# Fanout_Buffer.net
KiCad netlist of a schematic drawn in Altium Designer
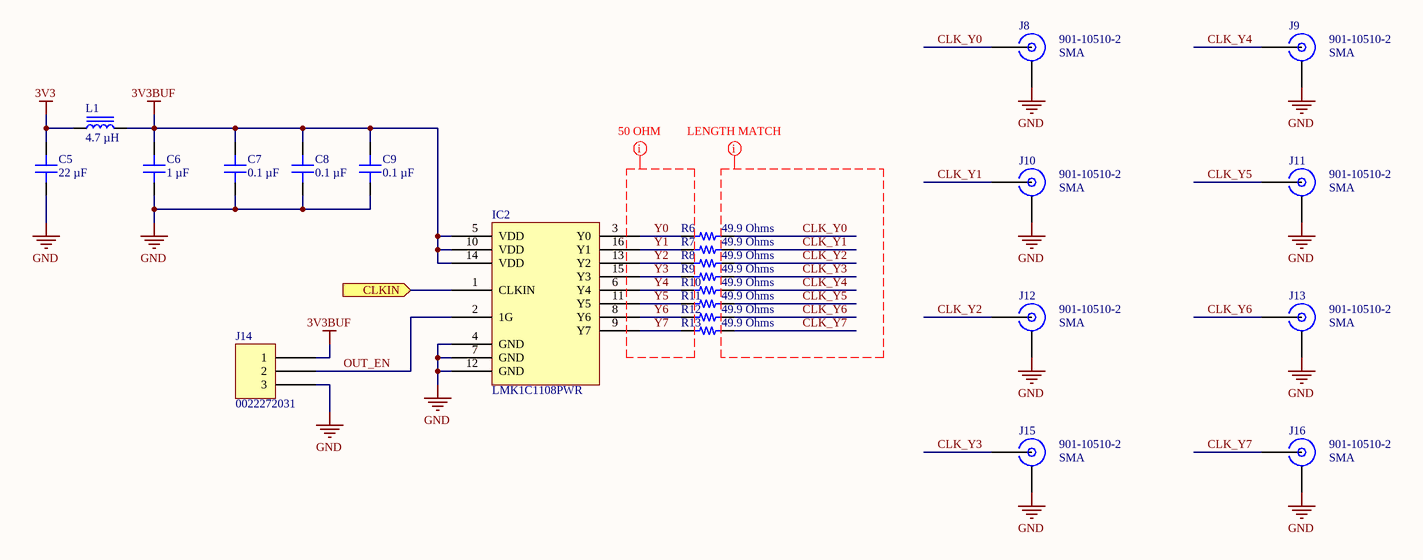
[diagram p0: Fanout Buffer.SchDoc]

(export (version "E")
  (design (tool "Eeschema 10.0.6"))
  (components
    (comp (ref "C5")
      (value "22 µF")
      (footprint "CAP 0603_1608")
      (description "CAP CER 22UF 10V X5R 0603")
      (fields
        (field (name "PART NUMBER") "CL10A226MP8NUNE")
        (field (name "MANUFACTURER") "Samsung Electro-Mechanics")
      )
      (libsource (lib "altiumlibrary.com") (part "Capacitor"))
    )
    (comp (ref "C6")
      (value "1 µF")
      (footprint "CAP 0603_1608")
      (description "CAP CER 1UF 25V X7R 0603")
      (fields
        (field (name "PART NUMBER") "GCM188R71E105KA64D")
        (field (name "MANUFACTURER") "Murata Electronics")
      )
      (libsource (lib "altiumlibrary.com") (part "Capacitor"))
    )
    (comp (ref "C7")
      (value "0.1 µF")
      (footprint "CAP 0603_1608")
      (description "CAP CER 0.1UF 50V X7R 0603")
      (fields
        (field (name "PART NUMBER") "CL10B104KB8NNNC")
        (field (name "MANUFACTURER") "Samsung Electro-Mechanics")
      )
      (libsource (lib "altiumlibrary.com") (part "Capacitor"))
    )
    (comp (ref "C8")
      (value "0.1 µF")
      (footprint "CAP 0603_1608")
      (description "CAP CER 0.1UF 50V X7R 0603")
      (fields
        (field (name "PART NUMBER") "CL10B104KB8NNNC")
        (field (name "MANUFACTURER") "Samsung Electro-Mechanics")
      )
      (libsource (lib "altiumlibrary.com") (part "Capacitor"))
    )
    (comp (ref "C9")
      (value "0.1 µF")
      (footprint "CAP 0603_1608")
      (description "CAP CER 0.1UF 50V X7R 0603")
      (fields
        (field (name "PART NUMBER") "CL10B104KB8NNNC")
        (field (name "MANUFACTURER") "Samsung Electro-Mechanics")
      )
      (libsource (lib "altiumlibrary.com") (part "Capacitor"))
    )
    (comp (ref "IC2")
      (value "LMK1C1108PWR")
      (footprint "TI TSSOP-16 PW0016A")
      (description "IC CLK BUFFER 1:8 250MHZ 16TSSOP")
      (fields (field (name "MANUFACTURER") "Texas Instruments"))
      (libsource (lib "altiumlibrary.com") (part "TI LMK1C1108 PW"))
    )
    (comp (ref "J8")
      (value "901-10510-2")
      (footprint "AMPHENOL 901-10510-2")
      (description "CONN SMA JACK R/A 50OHM EDGE MNT")
      (fields (field (name "CONNECTOR STYLE") "SMA") (field (name "MANUFACTURER") "Amphenol RF"))
      (libsource (lib "altiumlibrary.com") (part "COAXIAL JACK"))
    )
    (comp (ref "J9")
      (value "901-10510-2")
      (footprint "AMPHENOL 901-10510-2")
      (description "CONN SMA JACK R/A 50OHM EDGE MNT")
      (fields (field (name "CONNECTOR STYLE") "SMA") (field (name "MANUFACTURER") "Amphenol RF"))
      (libsource (lib "altiumlibrary.com") (part "COAXIAL JACK"))
    )
    (comp (ref "J10")
      (value "901-10510-2")
      (footprint "AMPHENOL 901-10510-2")
      (description "CONN SMA JACK R/A 50OHM EDGE MNT")
      (fields (field (name "CONNECTOR STYLE") "SMA") (field (name "MANUFACTURER") "Amphenol RF"))
      (libsource (lib "altiumlibrary.com") (part "COAXIAL JACK"))
    )
    (comp (ref "J11")
      (value "901-10510-2")
      (footprint "AMPHENOL 901-10510-2")
      (description "CONN SMA JACK R/A 50OHM EDGE MNT")
      (fields (field (name "CONNECTOR STYLE") "SMA") (field (name "MANUFACTURER") "Amphenol RF"))
      (libsource (lib "altiumlibrary.com") (part "COAXIAL JACK"))
    )
    (comp (ref "J12")
      (value "901-10510-2")
      (footprint "AMPHENOL 901-10510-2")
      (description "CONN SMA JACK R/A 50OHM EDGE MNT")
      (fields (field (name "CONNECTOR STYLE") "SMA") (field (name "MANUFACTURER") "Amphenol RF"))
      (libsource (lib "altiumlibrary.com") (part "COAXIAL JACK"))
    )
    (comp (ref "J13")
      (value "901-10510-2")
      (footprint "AMPHENOL 901-10510-2")
      (description "CONN SMA JACK R/A 50OHM EDGE MNT")
      (fields (field (name "CONNECTOR STYLE") "SMA") (field (name "MANUFACTURER") "Amphenol RF"))
      (libsource (lib "altiumlibrary.com") (part "COAXIAL JACK"))
    )
    (comp (ref "J14")
      (value "0022272031")
      (footprint "MOLEX KK 0022272031")
      (description "CONN HEADER VERT 3POS 2.54MM")
      (fields (field (name "MANUFACTURER") "Molex"))
      (libsource (lib "altiumlibrary.com") (part "3 Pin"))
    )
    (comp (ref "J15")
      (value "901-10510-2")
      (footprint "AMPHENOL 901-10510-2")
      (description "CONN SMA JACK R/A 50OHM EDGE MNT")
      (fields (field (name "CONNECTOR STYLE") "SMA") (field (name "MANUFACTURER") "Amphenol RF"))
      (libsource (lib "altiumlibrary.com") (part "COAXIAL JACK"))
    )
    (comp (ref "J16")
      (value "901-10510-2")
      (footprint "AMPHENOL 901-10510-2")
      (description "CONN SMA JACK R/A 50OHM EDGE MNT")
      (fields (field (name "CONNECTOR STYLE") "SMA") (field (name "MANUFACTURER") "Amphenol RF"))
      (libsource (lib "altiumlibrary.com") (part "COAXIAL JACK"))
    )
    (comp (ref "L1")
      (value "4.7 µH")
      (footprint "WURTH WE-LQS 3015")
      (description "FIXED IND 4.7UH 1.3A 96 MOHM SMD")
      (fields (field (name "PART NUMBER") "74404032047") (field (name "MANUFACTURER") "Würth Elektronik"))
      (libsource (lib "altiumlibrary.com") (part "Inductor"))
    )
    (comp (ref "R6")
      (value "49.9 Ohms")
      (footprint "RES 0402_1005")
      (description "RES SMD 49.9 OHM 1% 1/10W 0402")
      (fields
        (field (name "PART NUMBER") "ERJ-2RKF49R9X")
        (field (name "MANUFACTURER") "Panasonic Electronic Components")
      )
      (libsource (lib "altiumlibrary.com") (part "Resistor"))
    )
    (comp (ref "R7")
      (value "49.9 Ohms")
      (footprint "RES 0402_1005")
      (description "RES SMD 49.9 OHM 1% 1/10W 0402")
      (fields
        (field (name "PART NUMBER") "ERJ-2RKF49R9X")
        (field (name "MANUFACTURER") "Panasonic Electronic Components")
      )
      (libsource (lib "altiumlibrary.com") (part "Resistor"))
    )
    (comp (ref "R8")
      (value "49.9 Ohms")
      (footprint "RES 0402_1005")
      (description "RES SMD 49.9 OHM 1% 1/10W 0402")
      (fields
        (field (name "PART NUMBER") "ERJ-2RKF49R9X")
        (field (name "MANUFACTURER") "Panasonic Electronic Components")
      )
      (libsource (lib "altiumlibrary.com") (part "Resistor"))
    )
    (comp (ref "R9")
      (value "49.9 Ohms")
      (footprint "RES 0402_1005")
      (description "RES SMD 49.9 OHM 1% 1/10W 0402")
      (fields
        (field (name "PART NUMBER") "ERJ-2RKF49R9X")
        (field (name "MANUFACTURER") "Panasonic Electronic Components")
      )
      (libsource (lib "altiumlibrary.com") (part "Resistor"))
    )
    (comp (ref "R10")
      (value "49.9 Ohms")
      (footprint "RES 0402_1005")
      (description "RES SMD 49.9 OHM 1% 1/10W 0402")
      (fields
        (field (name "PART NUMBER") "ERJ-2RKF49R9X")
        (field (name "MANUFACTURER") "Panasonic Electronic Components")
      )
      (libsource (lib "altiumlibrary.com") (part "Resistor"))
    )
    (comp (ref "R11")
      (value "49.9 Ohms")
      (footprint "RES 0402_1005")
      (description "RES SMD 49.9 OHM 1% 1/10W 0402")
      (fields
        (field (name "PART NUMBER") "ERJ-2RKF49R9X")
        (field (name "MANUFACTURER") "Panasonic Electronic Components")
      )
      (libsource (lib "altiumlibrary.com") (part "Resistor"))
    )
    (comp (ref "R12")
      (value "49.9 Ohms")
      (footprint "RES 0402_1005")
      (description "RES SMD 49.9 OHM 1% 1/10W 0402")
      (fields
        (field (name "PART NUMBER") "ERJ-2RKF49R9X")
        (field (name "MANUFACTURER") "Panasonic Electronic Components")
      )
      (libsource (lib "altiumlibrary.com") (part "Resistor"))
    )
    (comp (ref "R13")
      (value "49.9 Ohms")
      (footprint "RES 0402_1005")
      (description "RES SMD 49.9 OHM 1% 1/10W 0402")
      (fields
        (field (name "PART NUMBER") "ERJ-2RKF49R9X")
        (field (name "MANUFACTURER") "Panasonic Electronic Components")
      )
      (libsource (lib "altiumlibrary.com") (part "Resistor"))
    )
  )
  (nets
    (net (code "1") (name "/CLKIN") (class "Default")
      (node (ref "IC2") (pin "1") (pinfunction "CLKIN_1") (pintype "passive"))
    )
    (net (code "2") (name "/CLK_Y0") (class "Default")
      (node (ref "J8") (pin "S") (pinfunction "SIGNAL_S") (pintype "passive"))
      (node (ref "R6") (pin "2") (pinfunction "2_2") (pintype "passive"))
    )
    (net (code "3") (name "/CLK_Y1") (class "Default")
      (node (ref "J10") (pin "S") (pinfunction "SIGNAL_S") (pintype "passive"))
      (node (ref "R7") (pin "2") (pinfunction "2_2") (pintype "passive"))
    )
    (net (code "4") (name "/CLK_Y2") (class "Default")
      (node (ref "J12") (pin "S") (pinfunction "SIGNAL_S") (pintype "passive"))
      (node (ref "R8") (pin "2") (pinfunction "2_2") (pintype "passive"))
    )
    (net (code "5") (name "/CLK_Y3") (class "Default")
      (node (ref "J15") (pin "S") (pinfunction "SIGNAL_S") (pintype "passive"))
      (node (ref "R9") (pin "2") (pinfunction "2_2") (pintype "passive"))
    )
    (net (code "6") (name "/CLK_Y4") (class "Default")
      (node (ref "J9") (pin "S") (pinfunction "SIGNAL_S") (pintype "passive"))
      (node (ref "R10") (pin "2") (pinfunction "2_2") (pintype "passive"))
    )
    (net (code "7") (name "/CLK_Y5") (class "Default")
      (node (ref "J11") (pin "S") (pinfunction "SIGNAL_S") (pintype "passive"))
      (node (ref "R11") (pin "2") (pinfunction "2_2") (pintype "passive"))
    )
    (net (code "8") (name "/CLK_Y6") (class "Default")
      (node (ref "J13") (pin "S") (pinfunction "SIGNAL_S") (pintype "passive"))
      (node (ref "R12") (pin "2") (pinfunction "2_2") (pintype "passive"))
    )
    (net (code "9") (name "/CLK_Y7") (class "Default")
      (node (ref "J16") (pin "S") (pinfunction "SIGNAL_S") (pintype "passive"))
      (node (ref "R13") (pin "2") (pinfunction "2_2") (pintype "passive"))
    )
    (net (code "10") (name "/OUT_EN") (class "Default")
      (node (ref "IC2") (pin "2") (pinfunction "1G_2") (pintype "passive"))
      (node (ref "J14") (pin "2") (pinfunction "2_2") (pintype "passive"))
    )
    (net (code "11") (name "/Y0") (class "Default")
      (node (ref "IC2") (pin "3") (pinfunction "Y0_3") (pintype "passive"))
      (node (ref "R6") (pin "1") (pinfunction "1_1") (pintype "passive"))
    )
    (net (code "12") (name "/Y1") (class "Default")
      (node (ref "IC2") (pin "16") (pinfunction "Y1_16") (pintype "passive"))
      (node (ref "R7") (pin "1") (pinfunction "1_1") (pintype "passive"))
    )
    (net (code "13") (name "/Y2") (class "Default")
      (node (ref "IC2") (pin "13") (pinfunction "Y2_13") (pintype "passive"))
      (node (ref "R8") (pin "1") (pinfunction "1_1") (pintype "passive"))
    )
    (net (code "14") (name "/Y3") (class "Default")
      (node (ref "IC2") (pin "15") (pinfunction "Y3_15") (pintype "passive"))
      (node (ref "R9") (pin "1") (pinfunction "1_1") (pintype "passive"))
    )
    (net (code "15") (name "/Y4") (class "Default")
      (node (ref "IC2") (pin "6") (pinfunction "Y4_6") (pintype "passive"))
      (node (ref "R10") (pin "1") (pinfunction "1_1") (pintype "passive"))
    )
    (net (code "16") (name "/Y5") (class "Default")
      (node (ref "IC2") (pin "11") (pinfunction "Y5_11") (pintype "passive"))
      (node (ref "R11") (pin "1") (pinfunction "1_1") (pintype "passive"))
    )
    (net (code "17") (name "/Y6") (class "Default")
      (node (ref "IC2") (pin "8") (pinfunction "Y6_8") (pintype "passive"))
      (node (ref "R12") (pin "1") (pinfunction "1_1") (pintype "passive"))
    )
    (net (code "18") (name "/Y7") (class "Default")
      (node (ref "IC2") (pin "9") (pinfunction "Y7_9") (pintype "passive"))
      (node (ref "R13") (pin "1") (pinfunction "1_1") (pintype "passive"))
    )
    (net (code "19") (name "3V3") (class "Default")
      (node (ref "C5") (pin "2") (pinfunction "2_2") (pintype "passive"))
      (node (ref "L1") (pin "1") (pinfunction "1_1") (pintype "passive"))
    )
    (net (code "20") (name "3V3BUF") (class "Default")
      (node (ref "C6") (pin "2") (pinfunction "2_2") (pintype "passive"))
      (node (ref "C7") (pin "1") (pinfunction "1_1") (pintype "passive"))
      (node (ref "C8") (pin "1") (pinfunction "1_1") (pintype "passive"))
      (node (ref "C9") (pin "1") (pinfunction "1_1") (pintype "passive"))
      (node (ref "IC2") (pin "10") (pinfunction "VDD_10") (pintype "passive"))
      (node (ref "IC2") (pin "14") (pinfunction "VDD_14") (pintype "passive"))
      (node (ref "IC2") (pin "5") (pinfunction "VDD_5") (pintype "passive"))
      (node (ref "J14") (pin "1") (pinfunction "1_1") (pintype "passive"))
      (node (ref "L1") (pin "2") (pinfunction "2_2") (pintype "passive"))
    )
    (net (code "21") (name "GND") (class "Default")
      (node (ref "C5") (pin "1") (pinfunction "1_1") (pintype "passive"))
      (node (ref "C6") (pin "1") (pinfunction "1_1") (pintype "passive"))
      (node (ref "C7") (pin "2") (pinfunction "2_2") (pintype "passive"))
      (node (ref "C8") (pin "2") (pinfunction "2_2") (pintype "passive"))
      (node (ref "C9") (pin "2") (pinfunction "2_2") (pintype "passive"))
      (node (ref "IC2") (pin "12") (pinfunction "GND_12") (pintype "passive"))
      (node (ref "IC2") (pin "4") (pinfunction "GND_4") (pintype "passive"))
      (node (ref "IC2") (pin "7") (pinfunction "GND_7") (pintype "passive"))
      (node (ref "J10") (pin "G") (pinfunction "GND_G") (pintype "passive"))
      (node (ref "J11") (pin "G") (pinfunction "GND_G") (pintype "passive"))
      (node (ref "J12") (pin "G") (pinfunction "GND_G") (pintype "passive"))
      (node (ref "J13") (pin "G") (pinfunction "GND_G") (pintype "passive"))
      (node (ref "J14") (pin "3") (pinfunction "3_3") (pintype "passive"))
      (node (ref "J15") (pin "G") (pinfunction "GND_G") (pintype "passive"))
      (node (ref "J16") (pin "G") (pinfunction "GND_G") (pintype "passive"))
      (node (ref "J8") (pin "G") (pinfunction "GND_G") (pintype "passive"))
      (node (ref "J9") (pin "G") (pinfunction "GND_G") (pintype "passive"))
    )
  )
)
